# LKS_074DO_0406.net
KiCad netlist of a schematic drawn in Altium Designer
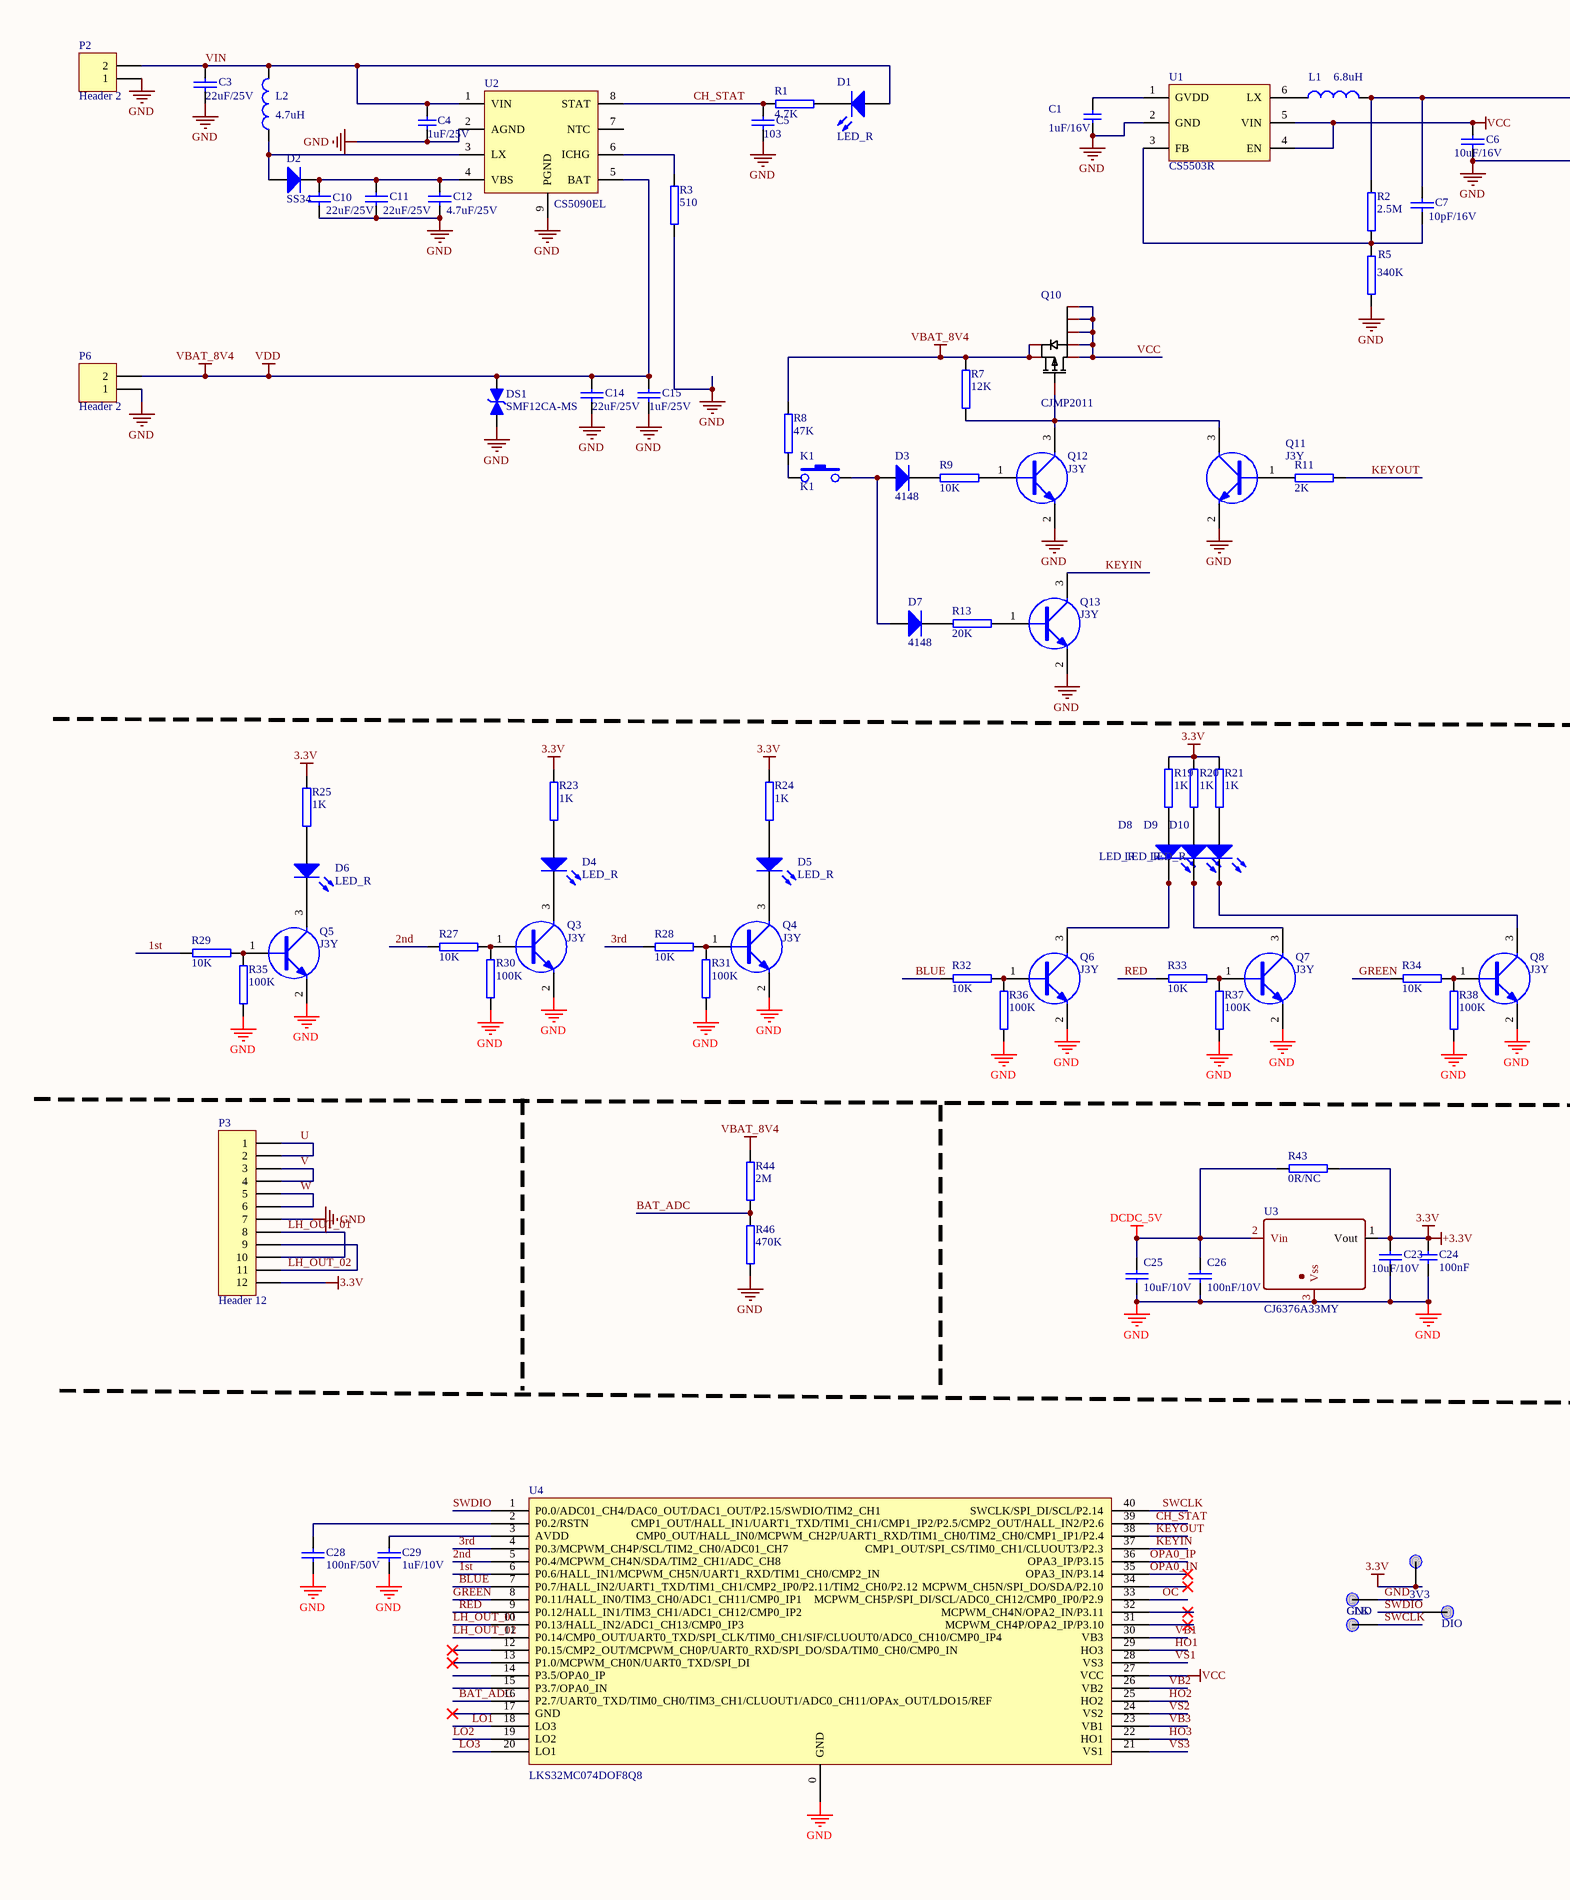
[diagram p0: LKS_074DO_0406.SchDoc, left]
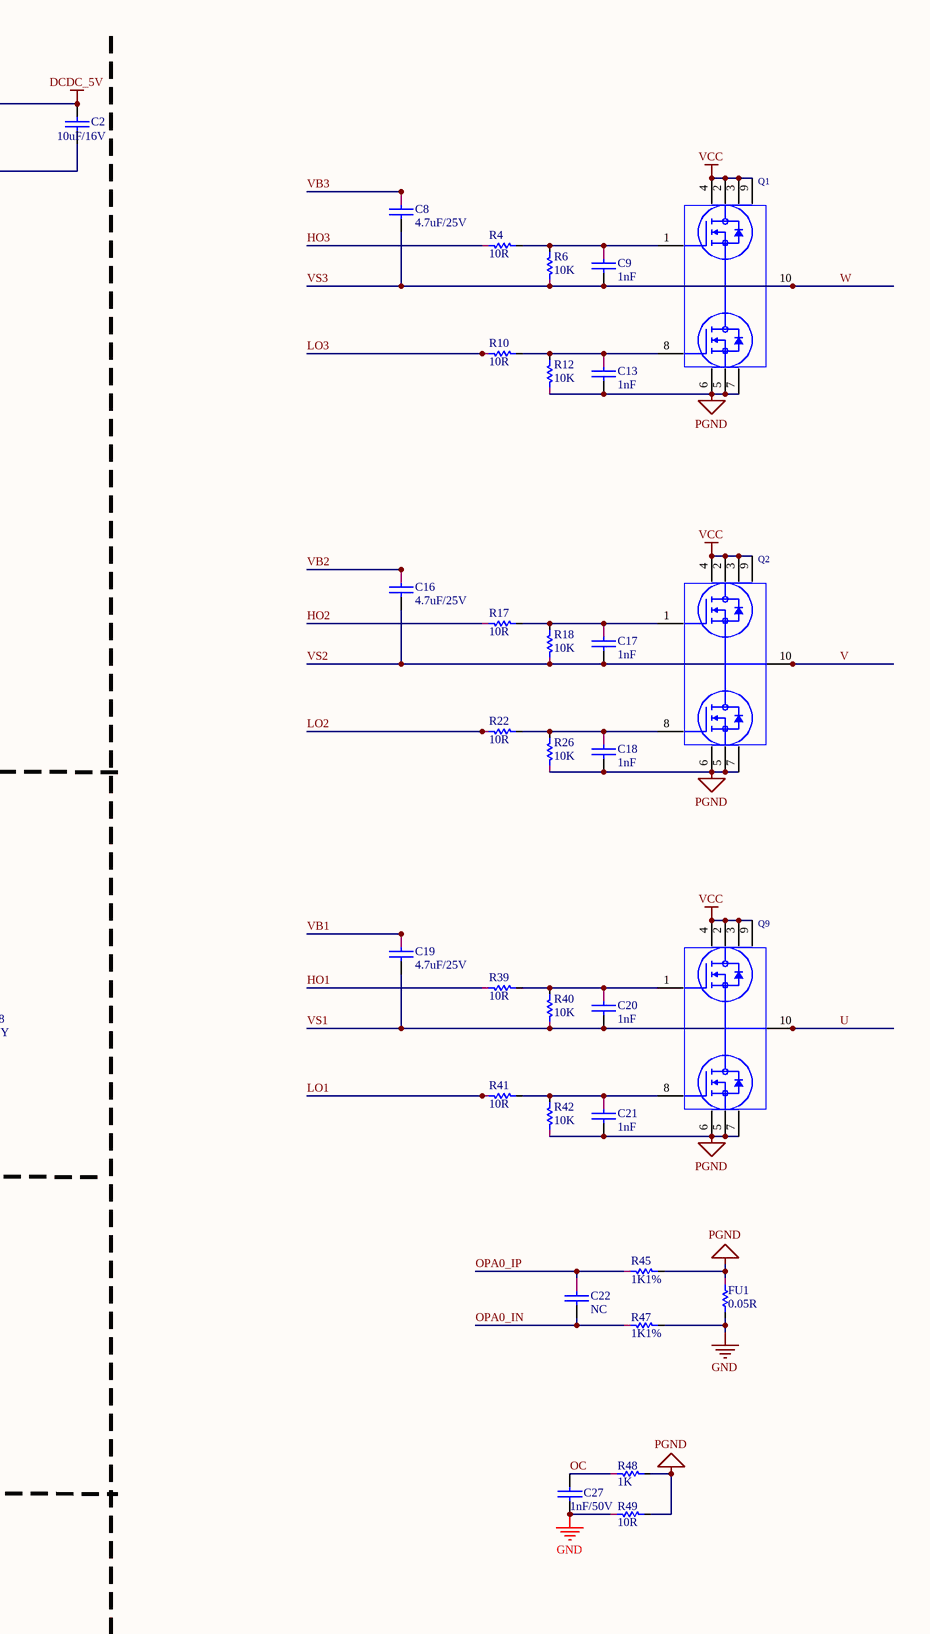
[diagram p1: LKS_074DO_0406.SchDoc, right]

(export (version "E")
  (design (tool "Eeschema 10.0.6"))
  (components
    (comp (ref "3V3") (value "test") (footprint "piot") (libsource (lib "LKS074DO_BRUSH_0329") (part "test")))
    (comp (ref "C1") (value "1uF/16V") (footprint "C 0402_M") (libsource (lib "") (part "CAP_2")))
    (comp (ref "C2")
      (value "10uF/16V")
      (footprint "C 0603_M")
      (description "Capacitor")
      (libsource (lib "") (part "CAP_1"))
    )
    (comp (ref "C3")
      (value "22uF/25V")
      (footprint "C 0603_M")
      (description "Capacitor")
      (libsource (lib "") (part "CAP_1"))
    )
    (comp (ref "C4") (value "1uF/25V") (footprint "C 0402_M") (libsource (lib "") (part "CAP_2")))
    (comp (ref "C5")
      (value "103")
      (footprint "R 0402_M")
      (description "Capacitor")
      (libsource (lib "") (part "CAP_1"))
    )
    (comp (ref "C6")
      (value "10uF/16V")
      (footprint "C 0603_M")
      (description "Capacitor")
      (libsource (lib "") (part "CAP_1"))
    )
    (comp (ref "C7")
      (value "10pF/16V")
      (footprint "C 0402_M")
      (description "Capacitor")
      (libsource (lib "") (part "CAP_1"))
    )
    (comp (ref "C8")
      (value "4.7uF/25V")
      (footprint "C 0402_M")
      (description "Capacitor")
      (libsource (lib "*") (part "CAP"))
    )
    (comp (ref "C9")
      (value "1nF")
      (footprint "C 0402_M")
      (description "Capacitor")
      (libsource (lib "*") (part "CAP"))
    )
    (comp (ref "C10")
      (value "22uF/25V")
      (footprint "C 0603_M")
      (description "Capacitor")
      (libsource (lib "") (part "CAP_1"))
    )
    (comp (ref "C11")
      (value "22uF/25V")
      (footprint "C 0603_M")
      (description "Capacitor")
      (libsource (lib "") (part "CAP_1"))
    )
    (comp (ref "C12")
      (value "4.7uF/25V")
      (footprint "C 0402_M")
      (description "Capacitor")
      (libsource (lib "") (part "CAP_1"))
    )
    (comp (ref "C13")
      (value "1nF")
      (footprint "C 0402_M")
      (description "Capacitor")
      (libsource (lib "*") (part "CAP"))
    )
    (comp (ref "C14")
      (value "22uF/25V")
      (footprint "C 0603_M")
      (description "Capacitor")
      (libsource (lib "") (part "CAP_1"))
    )
    (comp (ref "C15")
      (value "1uF/25V")
      (footprint "C 0402_M")
      (description "Capacitor")
      (libsource (lib "") (part "CAP_1"))
    )
    (comp (ref "C16")
      (value "4.7uF/25V")
      (footprint "C 0402_M")
      (description "Capacitor")
      (libsource (lib "*") (part "CAP"))
    )
    (comp (ref "C17")
      (value "1nF")
      (footprint "C 0402_M")
      (description "Capacitor")
      (libsource (lib "*") (part "CAP"))
    )
    (comp (ref "C18")
      (value "1nF")
      (footprint "C 0402_M")
      (description "Capacitor")
      (libsource (lib "*") (part "CAP"))
    )
    (comp (ref "C19")
      (value "4.7uF/25V")
      (footprint "C 0402_M")
      (description "Capacitor")
      (libsource (lib "*") (part "CAP"))
    )
    (comp (ref "C20")
      (value "1nF")
      (footprint "C 0402_M")
      (description "Capacitor")
      (libsource (lib "*") (part "CAP"))
    )
    (comp (ref "C21")
      (value "1nF")
      (footprint "C 0402_M")
      (description "Capacitor")
      (libsource (lib "*") (part "CAP"))
    )
    (comp (ref "C22")
      (value "NC")
      (footprint "C 0402_M")
      (description "Capacitor")
      (libsource (lib "*") (part "CAP"))
    )
    (comp (ref "C23")
      (value "10uF/10V")
      (footprint "C 0603_M")
      (description "Capacitor")
      (libsource (lib "") (part "CAP_1"))
    )
    (comp (ref "C24") (value "100nF") (footprint "C 0402_M") (libsource (lib "") (part "CAP_2")))
    (comp (ref "C25")
      (value "10uF/10V")
      (footprint "C 0603_M")
      (description "Capacitor")
      (libsource (lib "") (part "CAP_1"))
    )
    (comp (ref "C26")
      (value "100nF/10V")
      (footprint "C 0402_M")
      (description "Capacitor")
      (libsource (lib "") (part "CAP_1"))
    )
    (comp (ref "C27")
      (value "1nF/50V")
      (footprint "C 0402_M")
      (description "Capacitor")
      (libsource (lib "*") (part "C"))
    )
    (comp (ref "C28")
      (value "100nF/50V")
      (footprint "C 0402_M")
      (description "Capacitor")
      (libsource (lib "*") (part "C"))
    )
    (comp (ref "C29")
      (value "1uF/10V")
      (footprint "C 0402_M")
      (description "Capacitor")
      (libsource (lib "*") (part "C"))
    )
    (comp (ref "CLK") (value "test") (footprint "piot") (libsource (lib "LKS074DO_BRUSH_0329") (part "test")))
    (comp (ref "D1") (value "LED_R") (footprint "0603-LED") (libsource (lib "PuXun1") (part "LED")))
    (comp (ref "D2")
      (value "SS34")
      (footprint "SOD123FL")
      (description "Default Diode")
      (fields (field (name "PUBLISHER") "Altium Limited"))
      (libsource (lib "LKS034DO_Motor_0520_1") (part "Diode"))
    )
    (comp (ref "D3")
      (value "4148")
      (footprint "SOD-323")
      (description "Default Diode")
      (fields (field (name "PUBLISHER") "Altium Limited"))
      (libsource (lib "LKS034DO_Motor_0520_1") (part "Diode"))
    )
    (comp (ref "D4") (value "LED_R") (footprint "0603-LED") (libsource (lib "PuXun1") (part "LED")))
    (comp (ref "D5") (value "LED_R") (footprint "0603-LED") (libsource (lib "PuXun1") (part "LED")))
    (comp (ref "D6") (value "LED_R") (footprint "0603-LED") (libsource (lib "PuXun1") (part "LED")))
    (comp (ref "D7")
      (value "4148")
      (footprint "SOD-323")
      (description "Default Diode")
      (fields (field (name "PUBLISHER") "Altium Limited"))
      (libsource (lib "LKS034DO_Motor_0520_1") (part "Diode"))
    )
    (comp (ref "D8") (value "LED_R") (footprint "0603-LED") (libsource (lib "PuXun1") (part "LED")))
    (comp (ref "D9") (value "LED_R") (footprint "0603-LED") (libsource (lib "PuXun1") (part "LED")))
    (comp (ref "D10") (value "LED_R") (footprint "0603-LED") (libsource (lib "PuXun1") (part "LED")))
    (comp (ref "DIO") (value "test") (footprint "piot") (libsource (lib "LKS074DO_BRUSH_0329") (part "test")))
    (comp (ref "DS1")
      (value "SMF12CA-MS")
      (footprint "SOD-123F")
      (description "12V/19.9V")
      (libsource (lib "*") (part "DIODE-3"))
    )
    (comp (ref "FU1") (value "0.05R") (footprint "R 0805_M") (libsource (lib "*") (part "RAS")))
    (comp (ref "GND") (value "test") (footprint "piot") (libsource (lib "LKS074DO_BRUSH_0329") (part "test")))
    (comp (ref "K1") (value "K1") (footprint "SMD3.3X3.3X2") (libsource (lib "SCHLIB_NEW") (part "K1")))
    (comp (ref "L1")
      (value "6.8uH")
      (footprint "SMD3.5X3 .2- duplicate")
      (description "Inductor")
      (fields (field (name "PUBLISHER") "Altium Limited"))
      (libsource (lib "Miscellaneous Devices") (part "Inductor"))
    )
    (comp (ref "L2")
      (value "4.7uH")
      (footprint "SMD3.5X3 .2- duplicate")
      (description "Inductor")
      (fields (field (name "PUBLISHER") "Altium Limited"))
      (libsource (lib "Miscellaneous Devices") (part "Inductor"))
    )
    (comp (ref "P2")
      (value "Header 2")
      (footprint "CONN_SMD_2P_0.6")
      (description "Header, 2-Pin")
      (fields (field (name "PUBLISHER") "Altium Limited"))
      (libsource (lib "Miscellaneous Connectors") (part "Header 2"))
    )
    (comp (ref "P3")
      (value "Header 12")
      (footprint "SMD-12")
      (description "Header, 12-Pin")
      (fields (field (name "PUBLISHER") "Altium Limited"))
      (libsource (lib "Miscellaneous Connectors") (part "Header 12"))
    )
    (comp (ref "P6")
      (value "Header 2")
      (footprint "CONN_SMD_2P_0.6")
      (description "Header, 2-Pin")
      (fields (field (name "PUBLISHER") "Altium Limited"))
      (libsource (lib "Miscellaneous Connectors") (part "Header 2"))
    )
    (comp (ref "Q1") (value "CJBM3020") (footprint "DFN-3X3_8") (libsource (lib "*") (part "CJBM3020")))
    (comp (ref "Q2") (value "CJBM3020") (footprint "DFN-3X3_8") (libsource (lib "*") (part "CJBM3020")))
    (comp (ref "Q3")
      (value "J3Y")
      (footprint "SOT-23")
      (description "NPN Transistor")
      (libsource (lib "*") (part "NPN"))
    )
    (comp (ref "Q4")
      (value "J3Y")
      (footprint "SOT-23")
      (description "NPN Transistor")
      (libsource (lib "*") (part "NPN"))
    )
    (comp (ref "Q5")
      (value "J3Y")
      (footprint "SOT-23")
      (description "NPN Transistor")
      (libsource (lib "*") (part "NPN"))
    )
    (comp (ref "Q6")
      (value "J3Y")
      (footprint "SOT-23")
      (description "NPN Transistor")
      (libsource (lib "*") (part "NPN"))
    )
    (comp (ref "Q7")
      (value "J3Y")
      (footprint "SOT-23")
      (description "NPN Transistor")
      (libsource (lib "*") (part "NPN"))
    )
    (comp (ref "Q8")
      (value "J3Y")
      (footprint "SOT-23")
      (description "NPN Transistor")
      (libsource (lib "*") (part "NPN"))
    )
    (comp (ref "Q9") (value "CJBM3020") (footprint "DFN-3X3_8") (libsource (lib "*") (part "CJBM3020")))
    (comp (ref "Q10")
      (value "CJMP2011")
      (footprint "DFN-6-2X2")
      (libsource (lib "LKS074DO_BRUSH_0329") (part "CJMP2011"))
    )
    (comp (ref "Q11")
      (value "J3Y")
      (footprint "SOT-23")
      (description "NPN Transistor")
      (libsource (lib "*") (part "NPN"))
    )
    (comp (ref "Q12")
      (value "J3Y")
      (footprint "SOT-23")
      (description "NPN Transistor")
      (libsource (lib "*") (part "NPN"))
    )
    (comp (ref "Q13")
      (value "J3Y")
      (footprint "SOT-23")
      (description "NPN Transistor")
      (libsource (lib "*") (part "NPN"))
    )
    (comp (ref "R1") (value "4.7K") (footprint "C 0402_M") (libsource (lib "*") (part "RES2_S")))
    (comp (ref "R2") (value "2.5M") (footprint "C 0402_M") (libsource (lib "*") (part "RES2_S")))
    (comp (ref "R3") (value "510") (footprint "R 0402_M") (libsource (lib "*") (part "RES2_S")))
    (comp (ref "R4") (value "10R") (footprint "R 0402_M") (libsource (lib "*") (part "RAS")))
    (comp (ref "R5") (value "340K") (footprint "C 0402_M") (libsource (lib "*") (part "RES2_S")))
    (comp (ref "R6") (value "10K") (footprint "R 0402_M") (libsource (lib "*") (part "RAS")))
    (comp (ref "R7") (value "12K") (footprint "C 0402_M") (libsource (lib "*") (part "RES2_S")))
    (comp (ref "R8") (value "47K") (footprint "C 0402_M") (libsource (lib "*") (part "RES2_S")))
    (comp (ref "R9") (value "10K") (footprint "C 0402_M") (libsource (lib "*") (part "RES2_S")))
    (comp (ref "R10") (value "10R") (footprint "R 0402_M") (libsource (lib "*") (part "RAS")))
    (comp (ref "R11") (value "2K") (footprint "C 0402_M") (libsource (lib "*") (part "RES2_S")))
    (comp (ref "R12") (value "10K") (footprint "R 0402_M") (libsource (lib "*") (part "RAS")))
    (comp (ref "R13") (value "20K") (footprint "C 0402_M") (libsource (lib "*") (part "RES2_S")))
    (comp (ref "R17") (value "10R") (footprint "R 0402_M") (libsource (lib "*") (part "RAS")))
    (comp (ref "R18") (value "10K") (footprint "R 0402_M") (libsource (lib "*") (part "RAS")))
    (comp (ref "R19") (value "1K") (footprint "C 0402_M") (libsource (lib "*") (part "RES2_S")))
    (comp (ref "R20") (value "1K") (footprint "C 0402_M") (libsource (lib "*") (part "RES2_S")))
    (comp (ref "R21") (value "1K") (footprint "C 0402_M") (libsource (lib "*") (part "RES2_S")))
    (comp (ref "R22") (value "10R") (footprint "R 0402_M") (libsource (lib "*") (part "RAS")))
    (comp (ref "R23") (value "1K") (footprint "C 0402_M") (libsource (lib "*") (part "RES2_S")))
    (comp (ref "R24") (value "1K") (footprint "C 0402_M") (libsource (lib "*") (part "RES2_S")))
    (comp (ref "R25") (value "1K") (footprint "C 0402_M") (libsource (lib "*") (part "RES2_S")))
    (comp (ref "R26") (value "10K") (footprint "R 0402_M") (libsource (lib "*") (part "RAS")))
    (comp (ref "R27") (value "10K") (footprint "C 0402_M") (libsource (lib "*") (part "RES2_S")))
    (comp (ref "R28") (value "10K") (footprint "C 0402_M") (libsource (lib "*") (part "RES2_S")))
    (comp (ref "R29") (value "10K") (footprint "C 0402_M") (libsource (lib "*") (part "RES2_S")))
    (comp (ref "R30") (value "100K") (footprint "C 0402_M") (libsource (lib "*") (part "RES2_S")))
    (comp (ref "R31") (value "100K") (footprint "C 0402_M") (libsource (lib "*") (part "RES2_S")))
    (comp (ref "R32") (value "10K") (footprint "C 0402_M") (libsource (lib "*") (part "RES2_S")))
    (comp (ref "R33") (value "10K") (footprint "C 0402_M") (libsource (lib "*") (part "RES2_S")))
    (comp (ref "R34") (value "10K") (footprint "C 0402_M") (libsource (lib "*") (part "RES2_S")))
    (comp (ref "R35") (value "100K") (footprint "C 0402_M") (libsource (lib "*") (part "RES2_S")))
    (comp (ref "R36") (value "100K") (footprint "C 0402_M") (libsource (lib "*") (part "RES2_S")))
    (comp (ref "R37") (value "100K") (footprint "C 0402_M") (libsource (lib "*") (part "RES2_S")))
    (comp (ref "R38") (value "100K") (footprint "C 0402_M") (libsource (lib "*") (part "RES2_S")))
    (comp (ref "R39") (value "10R") (footprint "R 0402_M") (libsource (lib "*") (part "RAS")))
    (comp (ref "R40") (value "10K") (footprint "R 0402_M") (libsource (lib "*") (part "RAS")))
    (comp (ref "R41") (value "10R") (footprint "R 0402_M") (libsource (lib "*") (part "RAS")))
    (comp (ref "R42") (value "10K") (footprint "R 0402_M") (libsource (lib "*") (part "RAS")))
    (comp (ref "R43") (value "0R/NC") (footprint "0603") (libsource (lib "*") (part "RES2_S")))
    (comp (ref "R44") (value "2M") (footprint "C 0402_M") (libsource (lib "*") (part "RES2_S")))
    (comp (ref "R45") (value "1K1%") (footprint "R 0402_M") (libsource (lib "*") (part "RAS")))
    (comp (ref "R46") (value "470K") (footprint "C 0402_M") (libsource (lib "*") (part "RES2_S")))
    (comp (ref "R47") (value "1K1%") (footprint "R 0402_M") (libsource (lib "*") (part "RAS")))
    (comp (ref "R48") (value "1K") (footprint "R 0402_M") (libsource (lib "*") (part "RAS")))
    (comp (ref "R49") (value "10R") (footprint "R 0402_M") (libsource (lib "*") (part "RAS")))
    (comp (ref "U1")
      (value "CS5503R")
      (footprint "SOT23-6L")
      (libsource (lib "LKS034DO_Motor_0520_1") (part "CS5503R"))
    )
    (comp (ref "U2")
      (value "CS5090EL")
      (footprint "DFN2X2_8_0.5")
      (libsource (lib "LKS034DO_Motor_0520_1") (part "CS5090EL"))
    )
    (comp (ref "U3")
      (value "CJ6376A33MY")
      (footprint "SOT-23")
      (libsource (lib "LKS034DO_Motor_0520_1") (part "78L15"))
    )
    (comp (ref "U4")
      (value "LKS32MC074DOF8Q8")
      (footprint "QFN40")
      (description "芯片")
      (libsource (lib "Q_LINKO_V1.0") (part "LKS32MC074DF8Q8"))
    )
  )
  (nets
    (net (code "1") (name "+3.3V") (class "Default")
      (node (ref "3V3") (pin "1") (pinfunction "1_1") (pintype "passive"))
      (node (ref "C23") (pin "2") (pinfunction "2_2") (pintype "passive"))
      (node (ref "C24") (pin "1") (pinfunction "1_1") (pintype "passive"))
      (node (ref "P3") (pin "12") (pinfunction "12_12") (pintype "passive"))
      (node (ref "R19") (pin "2") (pinfunction "2_2") (pintype "passive"))
      (node (ref "R20") (pin "2") (pinfunction "2_2") (pintype "passive"))
      (node (ref "R21") (pin "2") (pinfunction "2_2") (pintype "passive"))
      (node (ref "R23") (pin "2") (pinfunction "2_2") (pintype "passive"))
      (node (ref "R24") (pin "2") (pinfunction "2_2") (pintype "passive"))
      (node (ref "R25") (pin "2") (pinfunction "2_2") (pintype "passive"))
      (node (ref "R43") (pin "2") (pinfunction "2_2") (pintype "passive"))
      (node (ref "U3") (pin "1") (pinfunction "Vout_1") (pintype "passive"))
    )
    (net (code "2") (name "/1st") (class "Default")
      (node (ref "R29") (pin "2") (pinfunction "2_2") (pintype "passive"))
      (node (ref "U4") (pin "6") (pinfunction "P0.6/HALL_IN1/MCPWM_CH5N/UART1_RXD/TIM1_CH0/CMP2_IN_6") (pintype "passive"))
    )
    (net (code "3") (name "/2nd") (class "Default")
      (node (ref "R27") (pin "2") (pinfunction "2_2") (pintype "passive"))
      (node (ref "U4") (pin "5") (pinfunction "P0.4/MCPWM_CH4N/SDA/TIM2_CH1/ADC_CH8_5") (pintype "passive"))
    )
    (net (code "4") (name "/3rd") (class "Default")
      (node (ref "R28") (pin "2") (pinfunction "2_2") (pintype "passive"))
      (node (ref "U4") (pin "4") (pinfunction "P0.3/MCPWM_CH4P/SCL/TIM2_CH0/ADC01_CH7_4") (pintype "passive"))
    )
    (net (code "5") (name "/BAT_ADC") (class "Default")
      (node (ref "R44") (pin "2") (pinfunction "2_2") (pintype "passive"))
      (node (ref "R46") (pin "1") (pinfunction "1_1") (pintype "passive"))
      (node (ref "U4") (pin "16") (pinfunction "P2.7/UART0_TXD/TIM0_CH0/TIM3_CH1/CLUOUT1/ADC0_CH11/OPAx_OUT/LDO15/REF_16") (pintype "passive"))
    )
    (net (code "6") (name "/BLUE") (class "Default")
      (node (ref "R32") (pin "2") (pinfunction "2_2") (pintype "passive"))
      (node (ref "U4") (pin "7") (pinfunction "P0.7/HALL_IN2/UART1_TXD/TIM1_CH1/CMP2_IP0/P2.11/TIM2_CH0/P2.12_7") (pintype "passive"))
    )
    (net (code "7") (name "/CH_STAT") (class "Default")
      (node (ref "C5") (pin "2") (pinfunction "2_2") (pintype "passive"))
      (node (ref "R1") (pin "1") (pinfunction "1_1") (pintype "passive"))
      (node (ref "U2") (pin "8") (pinfunction "STAT_8") (pintype "passive"))
      (node (ref "U4") (pin "39") (pinfunction "CMP1_OUT/HALL_IN1/UART1_TXD/TIM1_CH1/CMP1_IP2/P2.5/CMP2_OUT/HALL_IN2/P2.6_39") (pintype "passive"))
    )
    (net (code "8") (name "/GREEN") (class "Default")
      (node (ref "R34") (pin "2") (pinfunction "2_2") (pintype "passive"))
      (node (ref "U4") (pin "8") (pinfunction "P0.11/HALL_IN0/TIM3_CH0/ADC1_CH11/CMP0_IP1_8") (pintype "passive"))
    )
    (net (code "9") (name "/HO1") (class "Default")
      (node (ref "R39") (pin "2") (pinfunction "2_2") (pintype "passive"))
      (node (ref "U4") (pin "29") (pinfunction "HO3_29") (pintype "passive"))
    )
    (net (code "10") (name "/HO2") (class "Default")
      (node (ref "R17") (pin "2") (pinfunction "2_2") (pintype "passive"))
      (node (ref "U4") (pin "25") (pinfunction "HO2_25") (pintype "passive"))
    )
    (net (code "11") (name "/HO3") (class "Default")
      (node (ref "R4") (pin "2") (pinfunction "2_2") (pintype "passive"))
      (node (ref "U4") (pin "22") (pinfunction "HO1_22") (pintype "passive"))
    )
    (net (code "12") (name "/KEYIN") (class "Default")
      (node (ref "Q13") (pin "3") (pinfunction "C_3") (pintype "passive"))
      (node (ref "U4") (pin "37") (pinfunction "CMP1_OUT/SPI_CS/TIM0_CH1/CLUOUT3/P2.3_37") (pintype "passive"))
    )
    (net (code "13") (name "/KEYOUT") (class "Default")
      (node (ref "R11") (pin "2") (pinfunction "2_2") (pintype "passive"))
      (node (ref "U4") (pin "38") (pinfunction "CMP0_OUT/HALL_IN0/MCPWM_CH2P/UART1_RXD/TIM1_CH0/TIM2_CH0/CMP1_IP1/P2.4_38") (pintype "passive"))
    )
    (net (code "14") (name "/LH_OUT_01") (class "Default")
      (node (ref "P3") (pin "10") (pinfunction "10_10") (pintype "passive"))
      (node (ref "P3") (pin "8") (pinfunction "8_8") (pintype "passive"))
      (node (ref "U4") (pin "10") (pinfunction "P0.13/HALL_IN2/ADC1_CH13/CMP0_IP3_10") (pintype "passive"))
    )
    (net (code "15") (name "/LH_OUT_02") (class "Default")
      (node (ref "P3") (pin "11") (pinfunction "11_11") (pintype "passive"))
      (node (ref "P3") (pin "9") (pinfunction "9_9") (pintype "passive"))
      (node (ref "U4") (pin "11") (pinfunction "P0.14/CMP0_OUT/UART0_TXD/SPI_CLK/TIM0_CH1/SIF/CLUOUT0/ADC0_CH10/CMP0_IP4_11") (pintype "passive"))
    )
    (net (code "16") (name "/LO1") (class "Default")
      (node (ref "R41") (pin "2") (pinfunction "2_2") (pintype "passive"))
      (node (ref "U4") (pin "18") (pinfunction "LO3_18") (pintype "passive"))
    )
    (net (code "17") (name "/LO2") (class "Default")
      (node (ref "R22") (pin "2") (pinfunction "2_2") (pintype "passive"))
      (node (ref "U4") (pin "19") (pinfunction "LO2_19") (pintype "passive"))
    )
    (net (code "18") (name "/LO3") (class "Default")
      (node (ref "R10") (pin "2") (pinfunction "2_2") (pintype "passive"))
      (node (ref "U4") (pin "20") (pinfunction "LO1_20") (pintype "passive"))
    )
    (net (code "19") (name "/OC") (class "Default")
      (node (ref "C27") (pin "2") (pinfunction "2_2") (pintype "passive"))
      (node (ref "R48") (pin "2") (pinfunction "2_2") (pintype "passive"))
      (node (ref "U4") (pin "33") (pinfunction "MCPWM_CH5P/SPI_DI/SCL/ADC0_CH12/CMP0_IP0/P2.9_33") (pintype "passive"))
    )
    (net (code "20") (name "/OPA0_IN") (class "Default")
      (node (ref "C22") (pin "1") (pinfunction "1_1") (pintype "passive"))
      (node (ref "R47") (pin "2") (pinfunction "2_2") (pintype "passive"))
      (node (ref "U4") (pin "35") (pinfunction "OPA3_IN/P3.14_35") (pintype "passive"))
    )
    (net (code "21") (name "/OPA0_IP") (class "Default")
      (node (ref "C22") (pin "2") (pinfunction "2_2") (pintype "passive"))
      (node (ref "R45") (pin "2") (pinfunction "2_2") (pintype "passive"))
      (node (ref "U4") (pin "36") (pinfunction "OPA3_IP/P3.15_36") (pintype "passive"))
    )
    (net (code "22") (name "/RED") (class "Default")
      (node (ref "R33") (pin "2") (pinfunction "2_2") (pintype "passive"))
      (node (ref "U4") (pin "9") (pinfunction "P0.12/HALL_IN1/TIM3_CH1/ADC1_CH12/CMP0_IP2_9") (pintype "passive"))
    )
    (net (code "23") (name "/SWCLK") (class "Default")
      (node (ref "CLK") (pin "1") (pinfunction "1_1") (pintype "passive"))
      (node (ref "U4") (pin "40") (pinfunction "SWCLK/SPI_DI/SCL/P2.14_40") (pintype "passive"))
    )
    (net (code "24") (name "/SWDIO") (class "Default")
      (node (ref "DIO") (pin "1") (pinfunction "1_1") (pintype "passive"))
      (node (ref "U4") (pin "1") (pinfunction "P0.0/ADC01_CH4/DAC0_OUT/DAC1_OUT/P2.15/SWDIO/TIM2_CH1_1") (pintype "passive"))
    )
    (net (code "25") (name "/U") (class "Default")
      (node (ref "C19") (pin "1") (pinfunction "1_1") (pintype "passive"))
      (node (ref "C20") (pin "1") (pinfunction "1_1") (pintype "passive"))
      (node (ref "P3") (pin "1") (pinfunction "1_1") (pintype "passive"))
      (node (ref "P3") (pin "2") (pinfunction "2_2") (pintype "passive"))
      (node (ref "Q9") (pin "10") (pinfunction "S1/D2_10") (pintype "passive"))
      (node (ref "R40") (pin "2") (pinfunction "2_2") (pintype "passive"))
      (node (ref "U4") (pin "28") (pinfunction "VS3_28") (pintype "passive"))
    )
    (net (code "26") (name "/V") (class "Default")
      (node (ref "C16") (pin "1") (pinfunction "1_1") (pintype "passive"))
      (node (ref "C17") (pin "1") (pinfunction "1_1") (pintype "passive"))
      (node (ref "P3") (pin "3") (pinfunction "3_3") (pintype "passive"))
      (node (ref "P3") (pin "4") (pinfunction "4_4") (pintype "passive"))
      (node (ref "Q2") (pin "10") (pinfunction "S1/D2_10") (pintype "passive"))
      (node (ref "R18") (pin "2") (pinfunction "2_2") (pintype "passive"))
      (node (ref "U4") (pin "24") (pinfunction "VS2_24") (pintype "passive"))
    )
    (net (code "27") (name "/VB1") (class "Default")
      (node (ref "C19") (pin "2") (pinfunction "2_2") (pintype "passive"))
      (node (ref "U4") (pin "30") (pinfunction "VB3_30") (pintype "passive"))
    )
    (net (code "28") (name "/VB2") (class "Default")
      (node (ref "C16") (pin "2") (pinfunction "2_2") (pintype "passive"))
      (node (ref "U4") (pin "26") (pinfunction "VB2_26") (pintype "passive"))
    )
    (net (code "29") (name "/VB3") (class "Default")
      (node (ref "C8") (pin "2") (pinfunction "2_2") (pintype "passive"))
      (node (ref "U4") (pin "23") (pinfunction "VB1_23") (pintype "passive"))
    )
    (net (code "30") (name "/VIN") (class "Default")
      (node (ref "C3") (pin "2") (pinfunction "2_2") (pintype "passive"))
      (node (ref "C4") (pin "1") (pinfunction "1_1") (pintype "passive"))
      (node (ref "D1") (pin "1") (pinfunction "A_1") (pintype "passive"))
      (node (ref "L2") (pin "2") (pinfunction "2_2") (pintype "passive"))
      (node (ref "P2") (pin "2") (pinfunction "2_2") (pintype "passive"))
      (node (ref "U2") (pin "1") (pinfunction "VIN_1") (pintype "passive"))
    )
    (net (code "31") (name "/VS3") (class "Default")
      (node (ref "C8") (pin "1") (pinfunction "1_1") (pintype "passive"))
      (node (ref "C9") (pin "1") (pinfunction "1_1") (pintype "passive"))
      (node (ref "P3") (pin "5") (pinfunction "5_5") (pintype "passive"))
      (node (ref "P3") (pin "6") (pinfunction "6_6") (pintype "passive"))
      (node (ref "Q1") (pin "10") (pinfunction "S1/D2_10") (pintype "passive"))
      (node (ref "R6") (pin "2") (pinfunction "2_2") (pintype "passive"))
      (node (ref "U4") (pin "21") (pinfunction "VS1_21") (pintype "passive"))
    )
    (net (code "32") (name "DCDC_5V") (class "Default")
      (node (ref "C2") (pin "2") (pinfunction "2_2") (pintype "passive"))
      (node (ref "C25") (pin "2") (pinfunction "2_2") (pintype "passive"))
      (node (ref "C26") (pin "1") (pinfunction "1_1") (pintype "passive"))
      (node (ref "C7") (pin "2") (pinfunction "2_2") (pintype "passive"))
      (node (ref "L1") (pin "2") (pinfunction "2_2") (pintype "passive"))
      (node (ref "R2") (pin "1") (pinfunction "1_1") (pintype "passive"))
      (node (ref "R43") (pin "1") (pinfunction "1_1") (pintype "passive"))
      (node (ref "U3") (pin "2") (pinfunction "Vin_2") (pintype "passive"))
    )
    (net (code "33") (name "GND") (class "Default")
      (node (ref "C1") (pin "1") (pinfunction "1_1") (pintype "passive"))
      (node (ref "C10") (pin "1") (pinfunction "1_1") (pintype "passive"))
      (node (ref "C11") (pin "1") (pinfunction "1_1") (pintype "passive"))
      (node (ref "C12") (pin "1") (pinfunction "1_1") (pintype "passive"))
      (node (ref "C14") (pin "1") (pinfunction "1_1") (pintype "passive"))
      (node (ref "C15") (pin "1") (pinfunction "1_1") (pintype "passive"))
      (node (ref "C2") (pin "1") (pinfunction "1_1") (pintype "passive"))
      (node (ref "C23") (pin "1") (pinfunction "1_1") (pintype "passive"))
      (node (ref "C24") (pin "2") (pinfunction "2_2") (pintype "passive"))
      (node (ref "C25") (pin "1") (pinfunction "1_1") (pintype "passive"))
      (node (ref "C26") (pin "2") (pinfunction "2_2") (pintype "passive"))
      (node (ref "C27") (pin "1") (pinfunction "1_1") (pintype "passive"))
      (node (ref "C28") (pin "2") (pinfunction "2_2") (pintype "passive"))
      (node (ref "C29") (pin "1") (pinfunction "1_1") (pintype "passive"))
      (node (ref "C3") (pin "1") (pinfunction "1_1") (pintype "passive"))
      (node (ref "C4") (pin "2") (pinfunction "2_2") (pintype "passive"))
      (node (ref "C5") (pin "1") (pinfunction "1_1") (pintype "passive"))
      (node (ref "C6") (pin "1") (pinfunction "1_1") (pintype "passive"))
      (node (ref "DS1") (pin "2") (pinfunction "K_2") (pintype "passive"))
      (node (ref "FU1") (pin "1") (pinfunction "1_1") (pintype "passive"))
      (node (ref "GND") (pin "1") (pinfunction "1_1") (pintype "passive"))
      (node (ref "P2") (pin "1") (pinfunction "1_1") (pintype "passive"))
      (node (ref "P3") (pin "7") (pinfunction "7_7") (pintype "passive"))
      (node (ref "P6") (pin "1") (pinfunction "1_1") (pintype "passive"))
      (node (ref "Q11") (pin "2") (pinfunction "E_2") (pintype "passive"))
      (node (ref "Q12") (pin "2") (pinfunction "E_2") (pintype "passive"))
      (node (ref "Q13") (pin "2") (pinfunction "E_2") (pintype "passive"))
      (node (ref "Q3") (pin "2") (pinfunction "E_2") (pintype "passive"))
      (node (ref "Q4") (pin "2") (pinfunction "E_2") (pintype "passive"))
      (node (ref "Q5") (pin "2") (pinfunction "E_2") (pintype "passive"))
      (node (ref "Q6") (pin "2") (pinfunction "E_2") (pintype "passive"))
      (node (ref "Q7") (pin "2") (pinfunction "E_2") (pintype "passive"))
      (node (ref "Q8") (pin "2") (pinfunction "E_2") (pintype "passive"))
      (node (ref "R3") (pin "2") (pinfunction "2_2") (pintype "passive"))
      (node (ref "R30") (pin "2") (pinfunction "2_2") (pintype "passive"))
      (node (ref "R31") (pin "2") (pinfunction "2_2") (pintype "passive"))
      (node (ref "R35") (pin "2") (pinfunction "2_2") (pintype "passive"))
      (node (ref "R36") (pin "2") (pinfunction "2_2") (pintype "passive"))
      (node (ref "R37") (pin "2") (pinfunction "2_2") (pintype "passive"))
      (node (ref "R38") (pin "2") (pinfunction "2_2") (pintype "passive"))
      (node (ref "R46") (pin "2") (pinfunction "2_2") (pintype "passive"))
      (node (ref "R47") (pin "1") (pinfunction "1_1") (pintype "passive"))
      (node (ref "R49") (pin "2") (pinfunction "2_2") (pintype "passive"))
      (node (ref "R5") (pin "2") (pinfunction "2_2") (pintype "passive"))
      (node (ref "U1") (pin "2") (pinfunction "GND_2") (pintype "passive"))
      (node (ref "U2") (pin "2") (pinfunction "AGND_2") (pintype "passive"))
      (node (ref "U2") (pin "9") (pinfunction "PGND_9") (pintype "passive"))
      (node (ref "U3") (pin "3") (pinfunction "Vss_3") (pintype "passive"))
      (node (ref "U4") (pin "0") (pinfunction "GND_0") (pintype "passive"))
    )
    (net (code "34") (name "Net-(D1-K)") (class "Default")
      (node (ref "D1") (pin "2") (pinfunction "K_2") (pintype "passive"))
      (node (ref "R1") (pin "2") (pinfunction "2_2") (pintype "passive"))
    )
    (net (code "35") (name "Net-(D2-A)") (class "Default")
      (node (ref "D2") (pin "1") (pinfunction "A_1") (pintype "passive"))
      (node (ref "L2") (pin "1") (pinfunction "1_1") (pintype "passive"))
      (node (ref "U2") (pin "3") (pinfunction "LX_3") (pintype "passive"))
    )
    (net (code "36") (name "Net-(D2-K)") (class "Default")
      (node (ref "C10") (pin "2") (pinfunction "2_2") (pintype "passive"))
      (node (ref "C11") (pin "2") (pinfunction "2_2") (pintype "passive"))
      (node (ref "C12") (pin "2") (pinfunction "2_2") (pintype "passive"))
      (node (ref "D2") (pin "2") (pinfunction "K_2") (pintype "passive"))
      (node (ref "U2") (pin "4") (pinfunction "VBS_4") (pintype "passive"))
    )
    (net (code "37") (name "Net-(D3-A)") (class "Default")
      (node (ref "D3") (pin "1") (pinfunction "A_1") (pintype "passive"))
      (node (ref "D7") (pin "1") (pinfunction "A_1") (pintype "passive"))
      (node (ref "K1") (pin "2") (pintype "passive"))
    )
    (net (code "38") (name "Net-(D3-K)") (class "Default")
      (node (ref "D3") (pin "2") (pinfunction "K_2") (pintype "passive"))
      (node (ref "R9") (pin "1") (pinfunction "1_1") (pintype "passive"))
    )
    (net (code "39") (name "Net-(D4-A)") (class "Default")
      (node (ref "D4") (pin "1") (pinfunction "A_1") (pintype "passive"))
      (node (ref "R23") (pin "1") (pinfunction "1_1") (pintype "passive"))
    )
    (net (code "40") (name "Net-(D4-K)") (class "Default")
      (node (ref "D4") (pin "2") (pinfunction "K_2") (pintype "passive"))
      (node (ref "Q3") (pin "3") (pinfunction "C_3") (pintype "passive"))
    )
    (net (code "41") (name "Net-(D5-A)") (class "Default")
      (node (ref "D5") (pin "1") (pinfunction "A_1") (pintype "passive"))
      (node (ref "R24") (pin "1") (pinfunction "1_1") (pintype "passive"))
    )
    (net (code "42") (name "Net-(D5-K)") (class "Default")
      (node (ref "D5") (pin "2") (pinfunction "K_2") (pintype "passive"))
      (node (ref "Q4") (pin "3") (pinfunction "C_3") (pintype "passive"))
    )
    (net (code "43") (name "Net-(D6-A)") (class "Default")
      (node (ref "D6") (pin "1") (pinfunction "A_1") (pintype "passive"))
      (node (ref "R25") (pin "1") (pinfunction "1_1") (pintype "passive"))
    )
    (net (code "44") (name "Net-(D6-K)") (class "Default")
      (node (ref "D6") (pin "2") (pinfunction "K_2") (pintype "passive"))
      (node (ref "Q5") (pin "3") (pinfunction "C_3") (pintype "passive"))
    )
    (net (code "45") (name "Net-(D7-K)") (class "Default")
      (node (ref "D7") (pin "2") (pinfunction "K_2") (pintype "passive"))
      (node (ref "R13") (pin "1") (pinfunction "1_1") (pintype "passive"))
    )
    (net (code "46") (name "Net-(D8-A)") (class "Default")
      (node (ref "D8") (pin "1") (pinfunction "A_1") (pintype "passive"))
      (node (ref "R19") (pin "1") (pinfunction "1_1") (pintype "passive"))
    )
    (net (code "47") (name "Net-(D8-K)") (class "Default")
      (node (ref "D8") (pin "2") (pinfunction "K_2") (pintype "passive"))
      (node (ref "Q6") (pin "3") (pinfunction "C_3") (pintype "passive"))
    )
    (net (code "48") (name "Net-(D9-A)") (class "Default")
      (node (ref "D9") (pin "1") (pinfunction "A_1") (pintype "passive"))
      (node (ref "R20") (pin "1") (pinfunction "1_1") (pintype "passive"))
    )
    (net (code "49") (name "Net-(D9-K)") (class "Default")
      (node (ref "D9") (pin "2") (pinfunction "K_2") (pintype "passive"))
      (node (ref "Q7") (pin "3") (pinfunction "C_3") (pintype "passive"))
    )
    (net (code "50") (name "Net-(D10-A)") (class "Default")
      (node (ref "D10") (pin "1") (pinfunction "A_1") (pintype "passive"))
      (node (ref "R21") (pin "1") (pinfunction "1_1") (pintype "passive"))
    )
    (net (code "51") (name "Net-(D10-K)") (class "Default")
      (node (ref "D10") (pin "2") (pinfunction "K_2") (pintype "passive"))
      (node (ref "Q8") (pin "3") (pinfunction "C_3") (pintype "passive"))
    )
    (net (code "52") (name "Net-(K1-Pad1)") (class "Default")
      (node (ref "K1") (pin "1") (pintype "passive"))
      (node (ref "R8") (pin "1") (pinfunction "1_1") (pintype "passive"))
    )
    (net (code "53") (name "Net-(Q1-G1)") (class "Default")
      (node (ref "C9") (pin "2") (pinfunction "2_2") (pintype "passive"))
      (node (ref "Q1") (pin "1") (pinfunction "G1_1") (pintype "passive"))
      (node (ref "R4") (pin "1") (pinfunction "1_1") (pintype "passive"))
      (node (ref "R6") (pin "1") (pinfunction "1_1") (pintype "passive"))
    )
    (net (code "54") (name "Net-(Q1-G2)") (class "Default")
      (node (ref "C13") (pin "2") (pinfunction "2_2") (pintype "passive"))
      (node (ref "Q1") (pin "8") (pinfunction "G2_8") (pintype "passive"))
      (node (ref "R10") (pin "1") (pinfunction "1_1") (pintype "passive"))
      (node (ref "R12") (pin "1") (pinfunction "1_1") (pintype "passive"))
    )
    (net (code "55") (name "Net-(Q2-G1)") (class "Default")
      (node (ref "C17") (pin "2") (pinfunction "2_2") (pintype "passive"))
      (node (ref "Q2") (pin "1") (pinfunction "G1_1") (pintype "passive"))
      (node (ref "R17") (pin "1") (pinfunction "1_1") (pintype "passive"))
      (node (ref "R18") (pin "1") (pinfunction "1_1") (pintype "passive"))
    )
    (net (code "56") (name "Net-(Q2-G2)") (class "Default")
      (node (ref "C18") (pin "2") (pinfunction "2_2") (pintype "passive"))
      (node (ref "Q2") (pin "8") (pinfunction "G2_8") (pintype "passive"))
      (node (ref "R22") (pin "1") (pinfunction "1_1") (pintype "passive"))
      (node (ref "R26") (pin "1") (pinfunction "1_1") (pintype "passive"))
    )
    (net (code "57") (name "Net-(Q3-B)") (class "Default")
      (node (ref "Q3") (pin "1") (pinfunction "B_1") (pintype "passive"))
      (node (ref "R27") (pin "1") (pinfunction "1_1") (pintype "passive"))
      (node (ref "R30") (pin "1") (pinfunction "1_1") (pintype "passive"))
    )
    (net (code "58") (name "Net-(Q4-B)") (class "Default")
      (node (ref "Q4") (pin "1") (pinfunction "B_1") (pintype "passive"))
      (node (ref "R28") (pin "1") (pinfunction "1_1") (pintype "passive"))
      (node (ref "R31") (pin "1") (pinfunction "1_1") (pintype "passive"))
    )
    (net (code "59") (name "Net-(Q5-B)") (class "Default")
      (node (ref "Q5") (pin "1") (pinfunction "B_1") (pintype "passive"))
      (node (ref "R29") (pin "1") (pinfunction "1_1") (pintype "passive"))
      (node (ref "R35") (pin "1") (pinfunction "1_1") (pintype "passive"))
    )
    (net (code "60") (name "Net-(Q6-B)") (class "Default")
      (node (ref "Q6") (pin "1") (pinfunction "B_1") (pintype "passive"))
      (node (ref "R32") (pin "1") (pinfunction "1_1") (pintype "passive"))
      (node (ref "R36") (pin "1") (pinfunction "1_1") (pintype "passive"))
    )
    (net (code "61") (name "Net-(Q7-B)") (class "Default")
      (node (ref "Q7") (pin "1") (pinfunction "B_1") (pintype "passive"))
      (node (ref "R33") (pin "1") (pinfunction "1_1") (pintype "passive"))
      (node (ref "R37") (pin "1") (pinfunction "1_1") (pintype "passive"))
    )
    (net (code "62") (name "Net-(Q8-B)") (class "Default")
      (node (ref "Q8") (pin "1") (pinfunction "B_1") (pintype "passive"))
      (node (ref "R34") (pin "1") (pinfunction "1_1") (pintype "passive"))
      (node (ref "R38") (pin "1") (pinfunction "1_1") (pintype "passive"))
    )
    (net (code "63") (name "Net-(Q9-G1)") (class "Default")
      (node (ref "C20") (pin "2") (pinfunction "2_2") (pintype "passive"))
      (node (ref "Q9") (pin "1") (pinfunction "G1_1") (pintype "passive"))
      (node (ref "R39") (pin "1") (pinfunction "1_1") (pintype "passive"))
      (node (ref "R40") (pin "1") (pinfunction "1_1") (pintype "passive"))
    )
    (net (code "64") (name "Net-(Q9-G2)") (class "Default")
      (node (ref "C21") (pin "2") (pinfunction "2_2") (pintype "passive"))
      (node (ref "Q9") (pin "8") (pinfunction "G2_8") (pintype "passive"))
      (node (ref "R41") (pin "1") (pinfunction "1_1") (pintype "passive"))
      (node (ref "R42") (pin "1") (pinfunction "1_1") (pintype "passive"))
    )
    (net (code "65") (name "Net-(Q10-G)") (class "Default")
      (node (ref "Q10") (pin "3") (pinfunction "G_3") (pintype "passive"))
      (node (ref "Q11") (pin "3") (pinfunction "C_3") (pintype "passive"))
      (node (ref "Q12") (pin "3") (pinfunction "C_3") (pintype "passive"))
      (node (ref "R7") (pin "1") (pinfunction "1_1") (pintype "passive"))
    )
    (net (code "66") (name "Net-(Q11-B)") (class "Default")
      (node (ref "Q11") (pin "1") (pinfunction "B_1") (pintype "passive"))
      (node (ref "R11") (pin "1") (pinfunction "1_1") (pintype "passive"))
    )
    (net (code "67") (name "Net-(Q12-B)") (class "Default")
      (node (ref "Q12") (pin "1") (pinfunction "B_1") (pintype "passive"))
      (node (ref "R9") (pin "2") (pinfunction "2_2") (pintype "passive"))
    )
    (net (code "68") (name "Net-(Q13-B)") (class "Default")
      (node (ref "Q13") (pin "1") (pinfunction "B_1") (pintype "passive"))
      (node (ref "R13") (pin "2") (pinfunction "2_2") (pintype "passive"))
    )
    (net (code "69") (name "Net-(U1-FB)") (class "Default")
      (node (ref "C7") (pin "1") (pinfunction "1_1") (pintype "passive"))
      (node (ref "R2") (pin "2") (pinfunction "2_2") (pintype "passive"))
      (node (ref "R5") (pin "1") (pinfunction "1_1") (pintype "passive"))
      (node (ref "U1") (pin "3") (pinfunction "FB_3") (pintype "passive"))
    )
    (net (code "70") (name "Net-(U1-GVDD)") (class "Default")
      (node (ref "C1") (pin "2") (pinfunction "2_2") (pintype "passive"))
      (node (ref "U1") (pin "1") (pinfunction "GVDD_1") (pintype "passive"))
    )
    (net (code "71") (name "Net-(U1-LX)") (class "Default")
      (node (ref "L1") (pin "1") (pinfunction "1_1") (pintype "passive"))
      (node (ref "U1") (pin "6") (pinfunction "LX_6") (pintype "passive"))
    )
    (net (code "72") (name "Net-(U2-ICHG)") (class "Default")
      (node (ref "R3") (pin "1") (pinfunction "1_1") (pintype "passive"))
      (node (ref "U2") (pin "6") (pinfunction "ICHG_6") (pintype "passive"))
    )
    (net (code "73") (name "Net-(U4-AVDD)") (class "Default")
      (node (ref "C29") (pin "2") (pinfunction "2_2") (pintype "passive"))
      (node (ref "U4") (pin "3") (pinfunction "AVDD_3") (pintype "passive"))
    )
    (net (code "74") (name "Net-(U4-P0.2{slash}RSTN)") (class "Default")
      (node (ref "C28") (pin "1") (pinfunction "1_1") (pintype "passive"))
      (node (ref "U4") (pin "2") (pinfunction "P0.2/RSTN_2") (pintype "passive"))
    )
    (net (code "75") (name "PGND") (class "Default")
      (node (ref "C13") (pin "1") (pinfunction "1_1") (pintype "passive"))
      (node (ref "C18") (pin "1") (pinfunction "1_1") (pintype "passive"))
      (node (ref "C21") (pin "1") (pinfunction "1_1") (pintype "passive"))
      (node (ref "FU1") (pin "2") (pinfunction "2_2") (pintype "passive"))
      (node (ref "Q1") (pin "5") (pinfunction "S2_5") (pintype "passive"))
      (node (ref "Q1") (pin "6") (pinfunction "S2_6") (pintype "passive"))
      (node (ref "Q1") (pin "7") (pinfunction "S2_7") (pintype "passive"))
      (node (ref "Q2") (pin "5") (pinfunction "S2_5") (pintype "passive"))
      (node (ref "Q2") (pin "6") (pinfunction "S2_6") (pintype "passive"))
      (node (ref "Q2") (pin "7") (pinfunction "S2_7") (pintype "passive"))
      (node (ref "Q9") (pin "5") (pinfunction "S2_5") (pintype "passive"))
      (node (ref "Q9") (pin "6") (pinfunction "S2_6") (pintype "passive"))
      (node (ref "Q9") (pin "7") (pinfunction "S2_7") (pintype "passive"))
      (node (ref "R12") (pin "2") (pinfunction "2_2") (pintype "passive"))
      (node (ref "R26") (pin "2") (pinfunction "2_2") (pintype "passive"))
      (node (ref "R42") (pin "2") (pinfunction "2_2") (pintype "passive"))
      (node (ref "R45") (pin "1") (pinfunction "1_1") (pintype "passive"))
      (node (ref "R48") (pin "1") (pinfunction "1_1") (pintype "passive"))
      (node (ref "R49") (pin "1") (pinfunction "1_1") (pintype "passive"))
    )
    (net (code "76") (name "VBAT_8V4") (class "Default")
      (node (ref "C14") (pin "2") (pinfunction "2_2") (pintype "passive"))
      (node (ref "C15") (pin "2") (pinfunction "2_2") (pintype "passive"))
      (node (ref "DS1") (pin "1") (pinfunction "A_1") (pintype "passive"))
      (node (ref "P6") (pin "2") (pinfunction "2_2") (pintype "passive"))
      (node (ref "Q10") (pin "4") (pinfunction "S_4") (pintype "passive"))
      (node (ref "Q10") (pin "8") (pinfunction "S_8") (pintype "passive"))
      (node (ref "R44") (pin "1") (pinfunction "1_1") (pintype "passive"))
      (node (ref "R7") (pin "2") (pinfunction "2_2") (pintype "passive"))
      (node (ref "R8") (pin "2") (pinfunction "2_2") (pintype "passive"))
      (node (ref "U2") (pin "5") (pinfunction "BAT_5") (pintype "passive"))
    )
    (net (code "77") (name "VCC") (class "Default")
      (node (ref "C6") (pin "2") (pinfunction "2_2") (pintype "passive"))
      (node (ref "Q1") (pin "2") (pinfunction "D1_2") (pintype "passive"))
      (node (ref "Q1") (pin "3") (pinfunction "D1_3") (pintype "passive"))
      (node (ref "Q1") (pin "4") (pinfunction "D1_4") (pintype "passive"))
      (node (ref "Q1") (pin "9") (pinfunction "D1_9") (pintype "passive"))
      (node (ref "Q10") (pin "1") (pinfunction "D_1") (pintype "passive"))
      (node (ref "Q10") (pin "2") (pinfunction "D_2") (pintype "passive"))
      (node (ref "Q10") (pin "5") (pinfunction "D_5") (pintype "passive"))
      (node (ref "Q10") (pin "6") (pinfunction "D_6") (pintype "passive"))
      (node (ref "Q10") (pin "7") (pinfunction "D_7") (pintype "passive"))
      (node (ref "Q2") (pin "2") (pinfunction "D1_2") (pintype "passive"))
      (node (ref "Q2") (pin "3") (pinfunction "D1_3") (pintype "passive"))
      (node (ref "Q2") (pin "4") (pinfunction "D1_4") (pintype "passive"))
      (node (ref "Q2") (pin "9") (pinfunction "D1_9") (pintype "passive"))
      (node (ref "Q9") (pin "2") (pinfunction "D1_2") (pintype "passive"))
      (node (ref "Q9") (pin "3") (pinfunction "D1_3") (pintype "passive"))
      (node (ref "Q9") (pin "4") (pinfunction "D1_4") (pintype "passive"))
      (node (ref "Q9") (pin "9") (pinfunction "D1_9") (pintype "passive"))
      (node (ref "U1") (pin "4") (pinfunction "EN_4") (pintype "passive"))
      (node (ref "U1") (pin "5") (pinfunction "VIN_5") (pintype "passive"))
      (node (ref "U4") (pin "27") (pinfunction "VCC_27") (pintype "passive"))
    )
    (net (code "78") (name "unconnected-(U2-NTC-Pad7)") (class "Default")
      (node (ref "U2") (pin "7") (pinfunction "NTC_7") (pintype "passive"))
    )
    (net (code "79") (name "unconnected-(U4-GND-Pad17)") (class "Default")
      (node (ref "U4") (pin "17") (pinfunction "GND_17") (pintype "passive+no_connect"))
    )
    (net (code "80") (name "unconnected-(U4-MCPWM_CH4N{slash}OPA2_IN{slash}P3.11-Pad32)") (class "Default")
      (node (ref "U4") (pin "32") (pinfunction "MCPWM_CH4N/OPA2_IN/P3.11_32") (pintype "passive"))
    )
    (net (code "81") (name "unconnected-(U4-MCPWM_CH4P{slash}OPA2_IP{slash}P3.10-Pad31)") (class "Default")
      (node (ref "U4") (pin "31") (pinfunction "MCPWM_CH4P/OPA2_IP/P3.10_31") (pintype "passive"))
    )
    (net (code "82") (name "unconnected-(U4-MCPWM_CH5N{slash}SPI_DO{slash}SDA{slash}P2.10-Pad34)") (class "Default")
      (node (ref "U4") (pin "34") (pinfunction "MCPWM_CH5N/SPI_DO/SDA/P2.10_34") (pintype "passive+no_connect"))
    )
    (net (code "83") (name "unconnected-(U4-P0.15{slash}CMP2_OUT{slash}MCPWM_CH0P{slash}UART0_RXD{slash}SPI_DO{slash}SDA{slash}TIM0_CH0{slash}CMP0_IN-Pad12)") (class "Default")
      (node (ref "U4") (pin "12") (pinfunction "P0.15/CMP2_OUT/MCPWM_CH0P/UART0_RXD/SPI_DO/SDA/TIM0_CH0/CMP0_IN_12") (pintype "passive+no_connect"))
    )
    (net (code "84") (name "unconnected-(U4-P1.0{slash}MCPWM_CH0N{slash}UART0_TXD{slash}SPI_DI-Pad13)") (class "Default")
      (node (ref "U4") (pin "13") (pinfunction "P1.0/MCPWM_CH0N/UART0_TXD/SPI_DI_13") (pintype "passive+no_connect"))
    )
    (net (code "85") (name "unconnected-(U4-P3.5{slash}OPA0_IP-Pad14)") (class "Default")
      (node (ref "U4") (pin "14") (pinfunction "P3.5/OPA0_IP_14") (pintype "passive"))
    )
    (net (code "86") (name "unconnected-(U4-P3.7{slash}OPA0_IN-Pad15)") (class "Default")
      (node (ref "U4") (pin "15") (pinfunction "P3.7/OPA0_IN_15") (pintype "passive"))
    )
  )
)
